# FAIO2_Sip-n-Puff.net
KiCad netlist of a schematic drawn in EAGLE
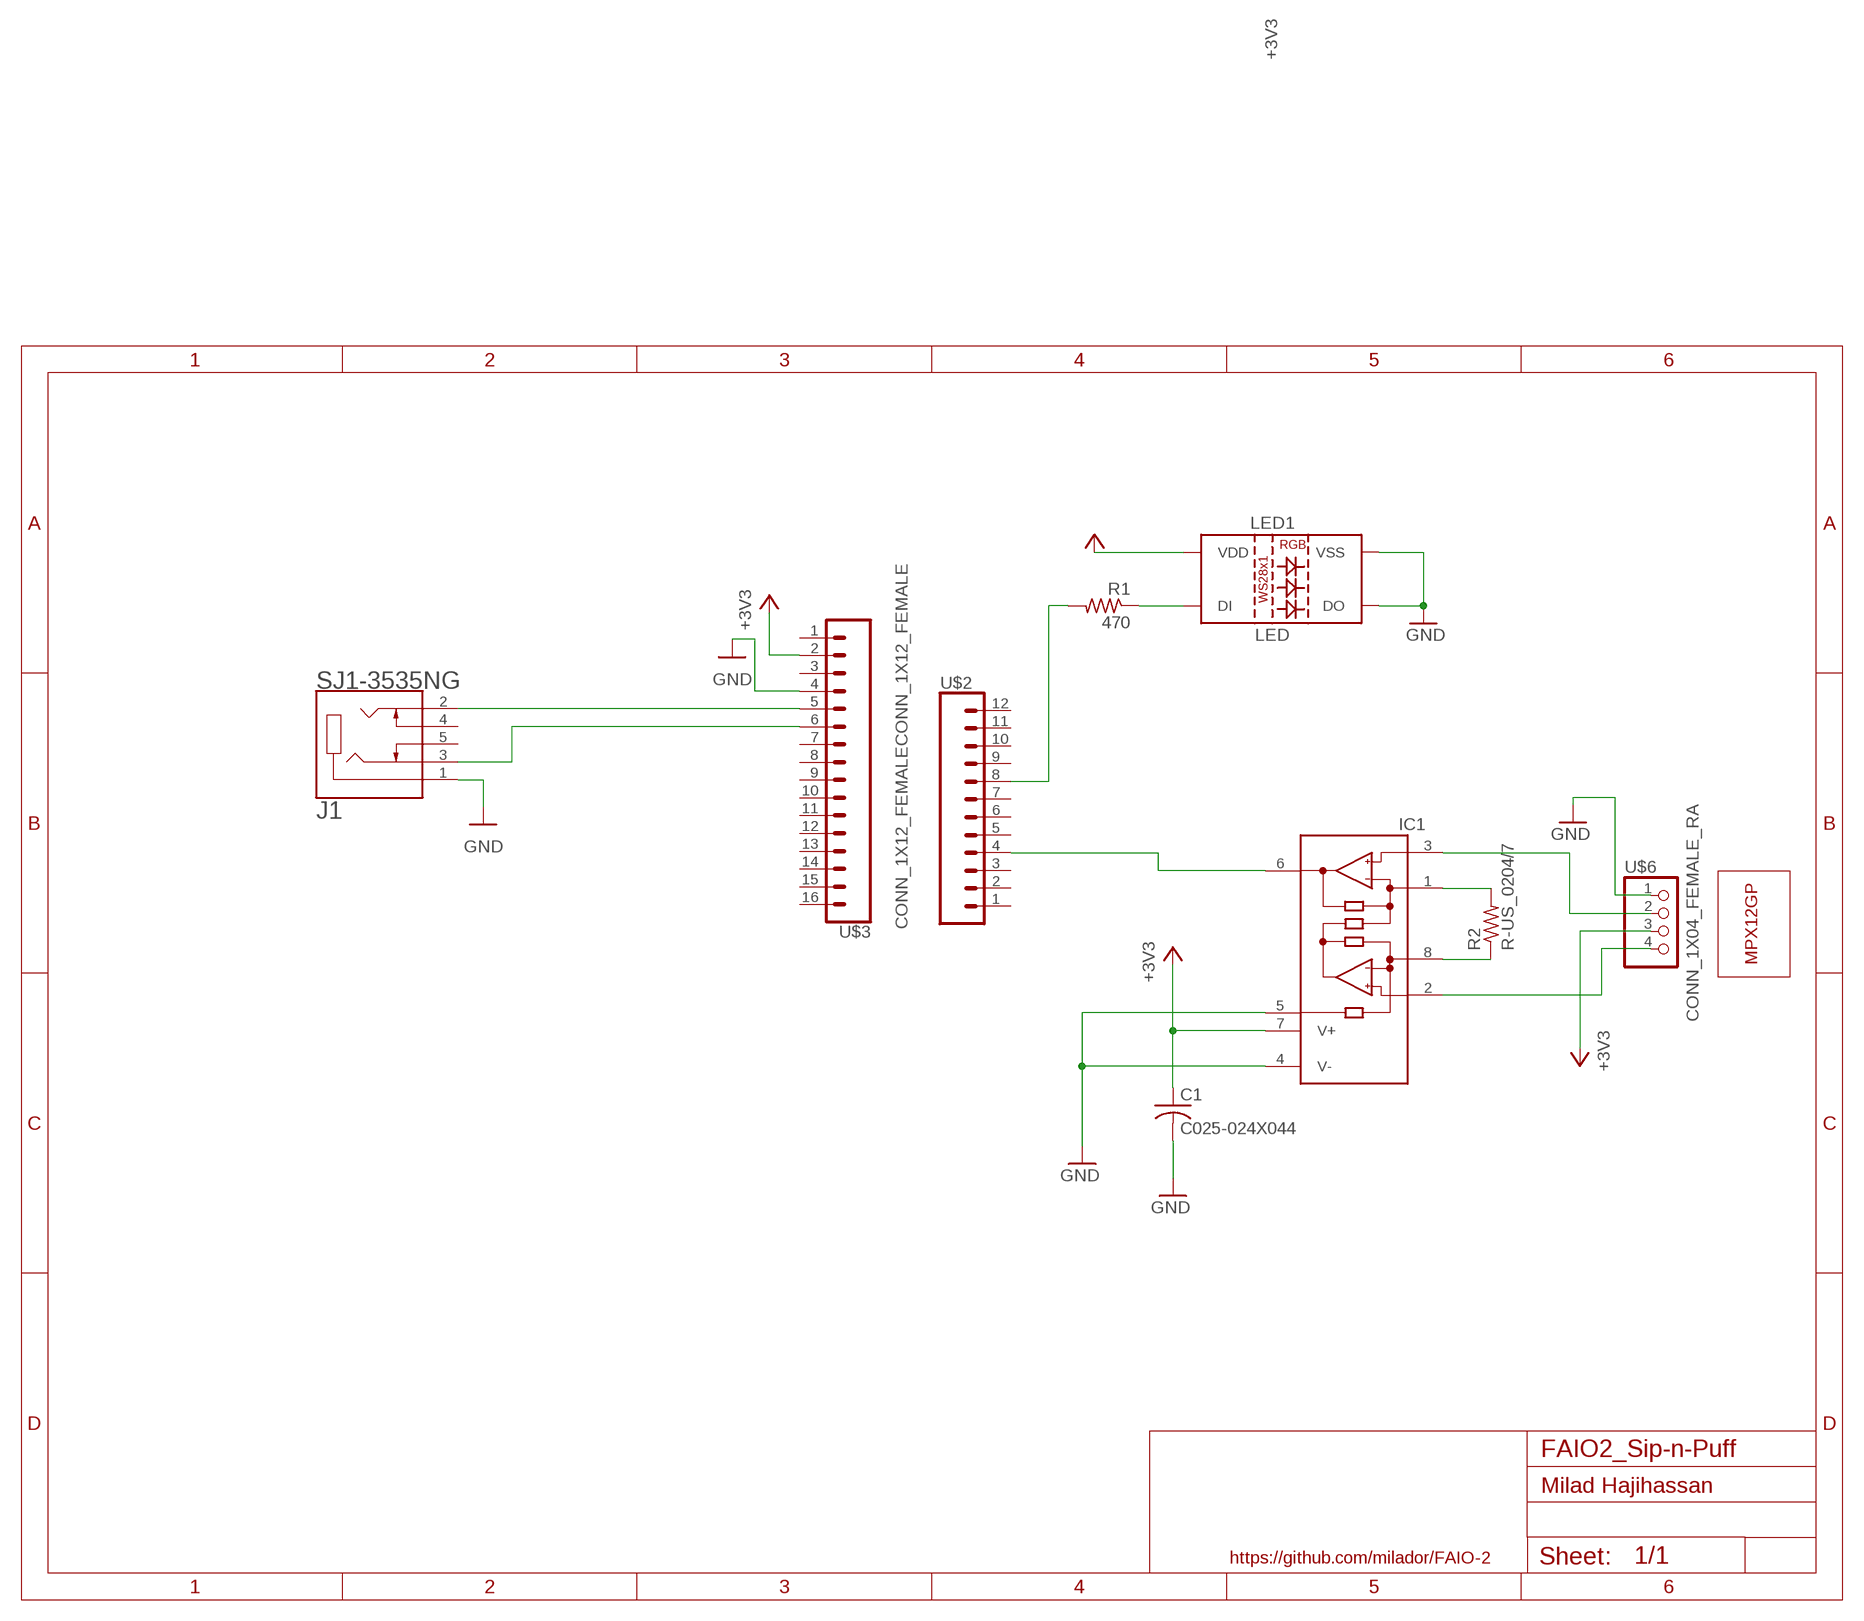
[diagram p0: schematic, sheet 1]

(export (version "E")
  (design (tool "Eeschema 10.0.6"))
  (components
    (comp (ref "C1")
      (value "C025-024X044")
      (footprint "eagle-import:C025-024X044")
      (libsource (lib "eagle-import") (part "C025-024X044"))
    )
    (comp (ref "IC1")
      (value "INA122PDIL08")
      (footprint "eagle-import:DIL08")
      (libsource (lib "eagle-import") (part "INA122PDIL08"))
    )
    (comp (ref "J1")
      (value "SJ1-3535NG")
      (footprint "eagle-import:CUI_SJ1-3535NG")
      (fields (field (name "MANUFACTURER") "CUI"))
      (libsource (lib "eagle-import") (part "SJ1-3535NG"))
    )
    (comp (ref "LED1")
      (value "LED")
      (footprint "eagle-import:NEOPIXELS-5MM")
      (libsource (lib "eagle-import") (part "NEOPIXELS-5MM"))
    )
    (comp (ref "R1")
      (value "470")
      (footprint "eagle-import:0204_7")
      (libsource (lib "eagle-import") (part "R-US_0204/7"))
    )
    (comp (ref "R2")
      (value "R-US_0204/7")
      (footprint "eagle-import:0204_7")
      (libsource (lib "eagle-import") (part "milador_9213569_R-US_0204/7"))
    )
    (comp (ref "U$1")
      (value "MPX12GPMPX12GP")
      (footprint "eagle-import:MPX")
      (libsource (lib "eagle-import") (part "MPX12GPMPX12GP"))
    )
    (comp (ref "U$2")
      (value "CONN_1X12_FEMALECONN_1X12_FEMALE")
      (footprint "eagle-import:CONN_1X12")
      (libsource (lib "eagle-import") (part "CONN_1X12_FEMALECONN_1X12_FEMALE"))
    )
    (comp (ref "U$3")
      (value "CONN_1X16_FEMALECONN_1X16_FEMALE")
      (footprint "eagle-import:CONN_1X16")
      (libsource (lib "eagle-import") (part "CONN_1X16_FEMALECONN_1X16_FEMALE"))
    )
    (comp (ref "U$6")
      (value "CONN_1X04_FEMALE_RA")
      (footprint "eagle-import:HDRRAR4W64P254_1X4_1066X850X254B")
      (libsource (lib "eagle-import") (part "CONN_1X04_FEMALE_RA"))
    )
  )
  (nets
    (net (code "1") (name "+3V3") (class "Default")
      (node (ref "C1") (pin "1") (pinfunction "1_1") (pintype "passive"))
      (node (ref "IC1") (pin "7") (pinfunction "V+_7") (pintype "power_in"))
      (node (ref "LED1") (pin "2") (pinfunction "VDD_2") (pintype "bidirectional"))
      (node (ref "U$3") (pin "2") (pinfunction "2_2") (pintype "passive"))
      (node (ref "U$6") (pin "3") (pinfunction "3_3") (pintype "passive"))
    )
    (net (code "2") (name "GND") (class "Default")
      (node (ref "C1") (pin "2") (pinfunction "2_2") (pintype "passive"))
      (node (ref "IC1") (pin "4") (pinfunction "V-_4") (pintype "power_in"))
      (node (ref "IC1") (pin "5") (pinfunction "REF_5") (pintype "passive"))
      (node (ref "J1") (pin "1") (pinfunction "1_1") (pintype "passive"))
      (node (ref "LED1") (pin "3") (pinfunction "VSS_3") (pintype "bidirectional"))
      (node (ref "LED1") (pin "4") (pinfunction "DO_4") (pintype "bidirectional"))
      (node (ref "U$3") (pin "4") (pinfunction "4_4") (pintype "passive"))
      (node (ref "U$6") (pin "1") (pinfunction "1_1") (pintype "passive"))
    )
    (net (code "3") (name "Net-(IC1-+IN)") (class "Default")
      (node (ref "IC1") (pin "3") (pinfunction "+IN_3") (pintype "input"))
      (node (ref "U$6") (pin "2") (pinfunction "2_2") (pintype "passive"))
    )
    (net (code "4") (name "Net-(IC1--IN)") (class "Default")
      (node (ref "IC1") (pin "2") (pinfunction "-IN_2") (pintype "input"))
      (node (ref "U$6") (pin "4") (pinfunction "4_4") (pintype "passive"))
    )
    (net (code "5") (name "Net-(IC1-OUT)") (class "Default")
      (node (ref "IC1") (pin "6") (pinfunction "OUT_6") (pintype "output"))
      (node (ref "U$2") (pin "4") (pinfunction "4_4") (pintype "passive"))
    )
    (net (code "6") (name "Net-(IC1-RG-Pad1)") (class "Default")
      (node (ref "IC1") (pin "1") (pinfunction "RG_1") (pintype "passive"))
      (node (ref "R2") (pin "2") (pinfunction "2_2") (pintype "passive"))
    )
    (net (code "7") (name "Net-(IC1-RG-Pad8)") (class "Default")
      (node (ref "IC1") (pin "8") (pinfunction "RG_8") (pintype "passive"))
      (node (ref "R2") (pin "1") (pinfunction "1_1") (pintype "passive"))
    )
    (net (code "8") (name "Net-(J1-Pad2)") (class "Default")
      (node (ref "J1") (pin "2") (pinfunction "2_2") (pintype "passive"))
      (node (ref "U$3") (pin "5") (pinfunction "5_5") (pintype "passive"))
    )
    (net (code "9") (name "Net-(J1-Pad3)") (class "Default")
      (node (ref "J1") (pin "3") (pinfunction "3_3") (pintype "passive"))
      (node (ref "U$3") (pin "6") (pinfunction "6_6") (pintype "passive"))
    )
    (net (code "10") (name "Net-(LED1-DI)") (class "Default")
      (node (ref "LED1") (pin "1") (pinfunction "DI_1") (pintype "bidirectional"))
      (node (ref "R1") (pin "1") (pinfunction "1_1") (pintype "passive"))
    )
    (net (code "11") (name "Net-(R1-Pad2)") (class "Default")
      (node (ref "R1") (pin "2") (pinfunction "2_2") (pintype "passive"))
      (node (ref "U$2") (pin "8") (pinfunction "8_8") (pintype "passive"))
    )
    (net (code "12") (name "unconnected-(J1-Pad4)") (class "Default")
      (node (ref "J1") (pin "4") (pinfunction "4_4") (pintype "passive"))
    )
    (net (code "13") (name "unconnected-(J1-Pad5)") (class "Default")
      (node (ref "J1") (pin "5") (pinfunction "5_5") (pintype "passive"))
    )
    (net (code "14") (name "unconnected-(U$2-Pad1)") (class "Default")
      (node (ref "U$2") (pin "1") (pinfunction "1_1") (pintype "passive"))
    )
    (net (code "15") (name "unconnected-(U$2-Pad2)") (class "Default")
      (node (ref "U$2") (pin "2") (pinfunction "2_2") (pintype "passive"))
    )
    (net (code "16") (name "unconnected-(U$2-Pad3)") (class "Default")
      (node (ref "U$2") (pin "3") (pinfunction "3_3") (pintype "passive"))
    )
    (net (code "17") (name "unconnected-(U$2-Pad5)") (class "Default")
      (node (ref "U$2") (pin "5") (pinfunction "5_5") (pintype "passive"))
    )
    (net (code "18") (name "unconnected-(U$2-Pad6)") (class "Default")
      (node (ref "U$2") (pin "6") (pinfunction "6_6") (pintype "passive"))
    )
    (net (code "19") (name "unconnected-(U$2-Pad7)") (class "Default")
      (node (ref "U$2") (pin "7") (pinfunction "7_7") (pintype "passive"))
    )
    (net (code "20") (name "unconnected-(U$2-Pad9)") (class "Default")
      (node (ref "U$2") (pin "9") (pinfunction "9_9") (pintype "passive"))
    )
    (net (code "21") (name "unconnected-(U$2-Pad10)") (class "Default")
      (node (ref "U$2") (pin "10") (pinfunction "10_10") (pintype "passive"))
    )
    (net (code "22") (name "unconnected-(U$2-Pad11)") (class "Default")
      (node (ref "U$2") (pin "11") (pinfunction "11_11") (pintype "passive"))
    )
    (net (code "23") (name "unconnected-(U$2-Pad12)") (class "Default")
      (node (ref "U$2") (pin "12") (pinfunction "12_12") (pintype "passive"))
    )
    (net (code "24") (name "unconnected-(U$3-Pad1)") (class "Default")
      (node (ref "U$3") (pin "1") (pinfunction "1_1") (pintype "passive"))
    )
    (net (code "25") (name "unconnected-(U$3-Pad3)") (class "Default")
      (node (ref "U$3") (pin "3") (pinfunction "3_3") (pintype "passive"))
    )
    (net (code "26") (name "unconnected-(U$3-Pad7)") (class "Default")
      (node (ref "U$3") (pin "7") (pinfunction "7_7") (pintype "passive"))
    )
    (net (code "27") (name "unconnected-(U$3-Pad8)") (class "Default")
      (node (ref "U$3") (pin "8") (pinfunction "8_8") (pintype "passive"))
    )
    (net (code "28") (name "unconnected-(U$3-Pad9)") (class "Default")
      (node (ref "U$3") (pin "9") (pinfunction "9_9") (pintype "passive"))
    )
    (net (code "29") (name "unconnected-(U$3-Pad10)") (class "Default")
      (node (ref "U$3") (pin "10") (pinfunction "10_10") (pintype "passive"))
    )
    (net (code "30") (name "unconnected-(U$3-Pad11)") (class "Default")
      (node (ref "U$3") (pin "11") (pinfunction "11_11") (pintype "passive"))
    )
    (net (code "31") (name "unconnected-(U$3-Pad12)") (class "Default")
      (node (ref "U$3") (pin "12") (pinfunction "12_12") (pintype "passive"))
    )
    (net (code "32") (name "unconnected-(U$3-Pad13)") (class "Default")
      (node (ref "U$3") (pin "13") (pinfunction "13_13") (pintype "passive"))
    )
    (net (code "33") (name "unconnected-(U$3-Pad14)") (class "Default")
      (node (ref "U$3") (pin "14") (pinfunction "14_14") (pintype "passive"))
    )
    (net (code "34") (name "unconnected-(U$3-Pad15)") (class "Default")
      (node (ref "U$3") (pin "15") (pinfunction "15_15") (pintype "passive"))
    )
    (net (code "35") (name "unconnected-(U$3-Pad16)") (class "Default")
      (node (ref "U$3") (pin "16") (pinfunction "16_16") (pintype "passive"))
    )
  )
)
